# shutter_board.net
KiCad netlist of a schematic drawn in EAGLE
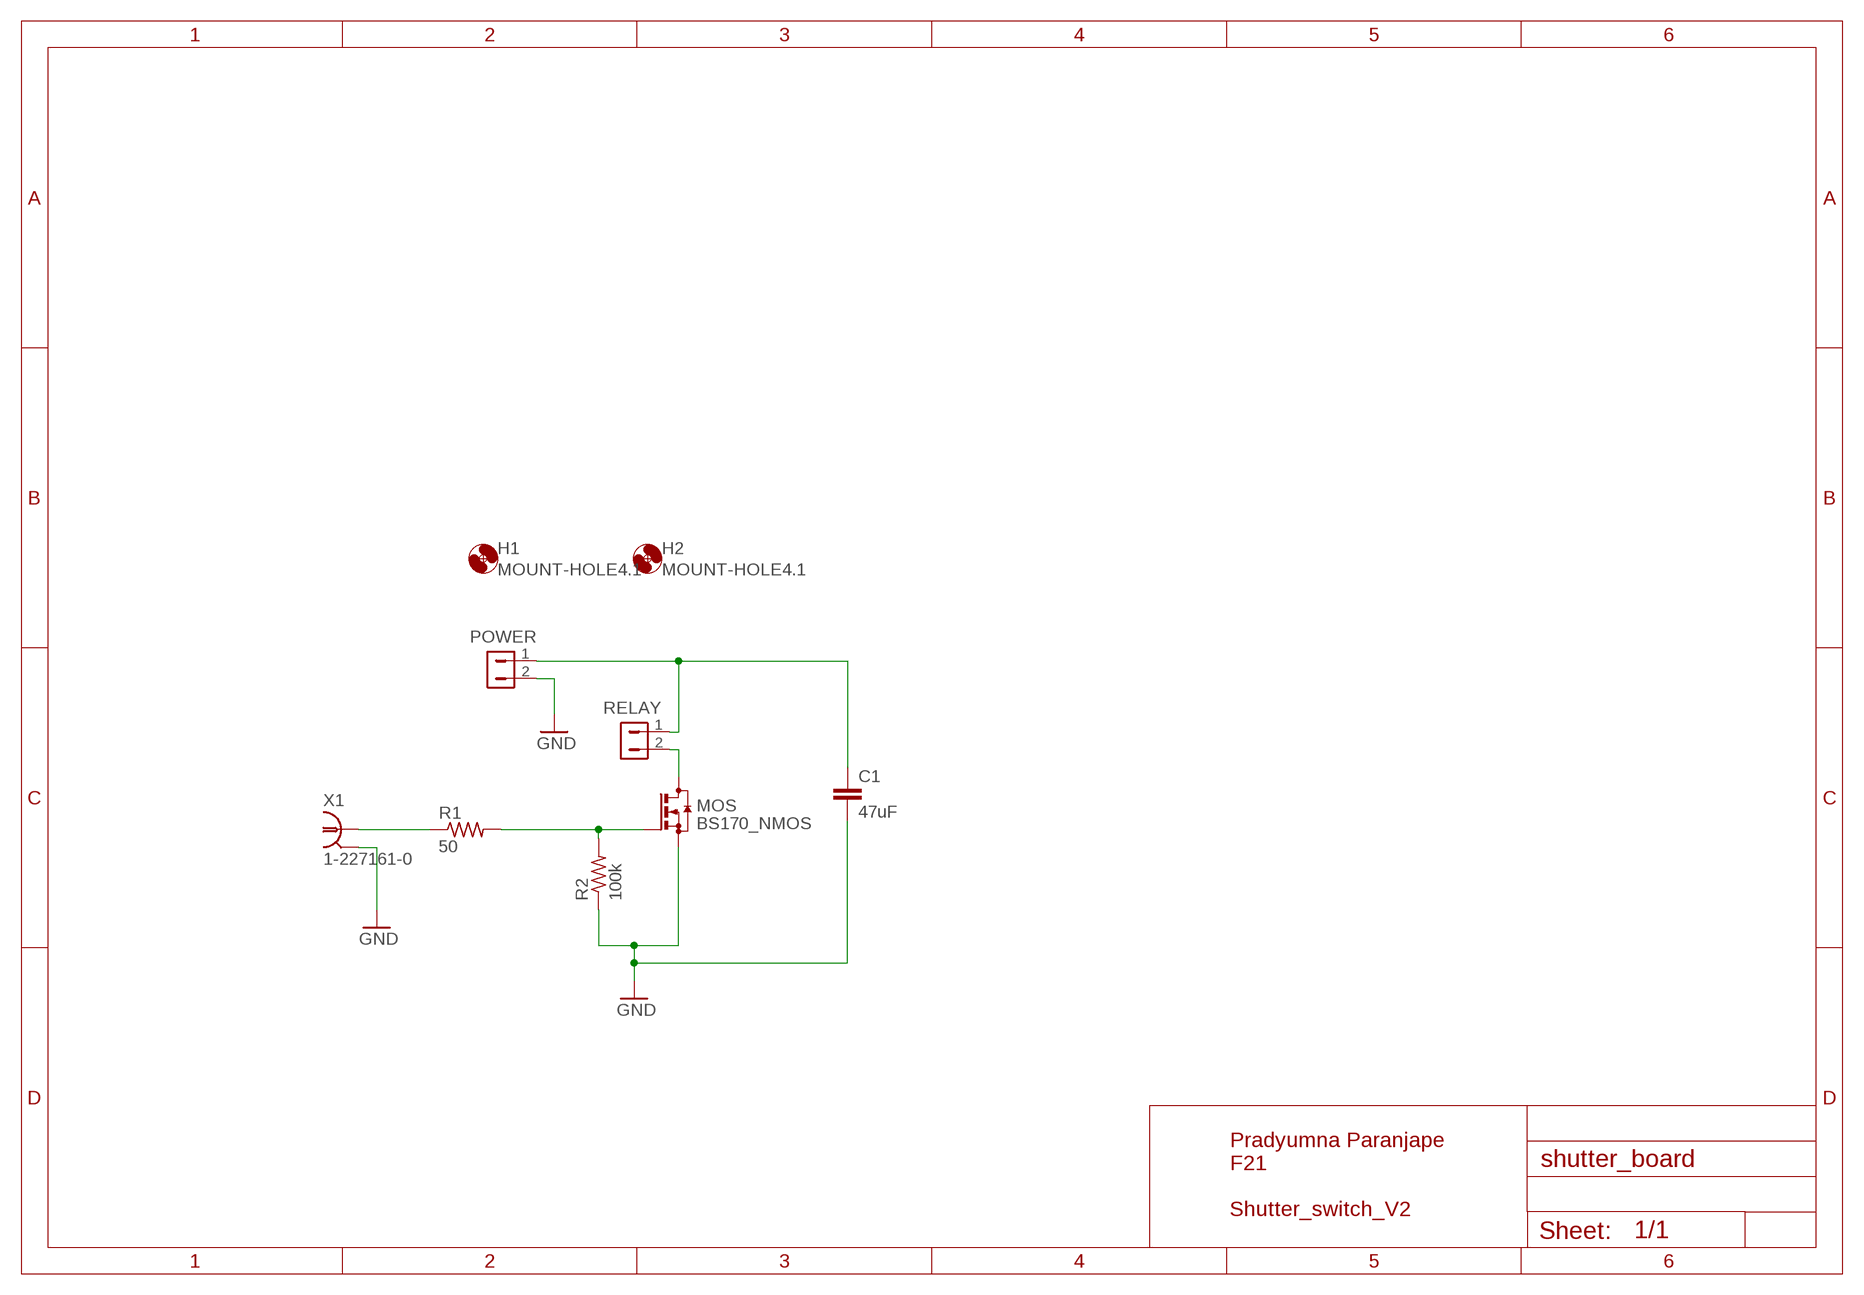
[diagram p0: schematic, sheet 1]

(export (version "E")
  (design (tool "Eeschema 10.0.6"))
  (components
    (comp (ref "C1")
      (value "47uF")
      (footprint "eagle-import:NALI_CAP")
      (libsource (lib "eagle-import") (part "NALI_CAPACITOR"))
    )
    (comp (ref "H1")
      (value "MOUNT-HOLE4.1")
      (footprint "eagle-import:4,1")
      (libsource (lib "eagle-import") (part "MOUNT-HOLE4.1"))
    )
    (comp (ref "H2")
      (value "MOUNT-HOLE4.1")
      (footprint "eagle-import:4,1")
      (libsource (lib "eagle-import") (part "MOUNT-HOLE4.1"))
    )
    (comp (ref "MOS")
      (value "BS170_NMOS")
      (footprint "eagle-import:TO92-3")
      (libsource (lib "eagle-import") (part "BS170_NMOS"))
    )
    (comp (ref "POWER")
      (value "2PIN_CONNECTOR")
      (footprint "eagle-import:KK2_MOLEX")
      (libsource (lib "eagle-import") (part "2PIN_CONNECTOR"))
    )
    (comp (ref "R1")
      (value "50")
      (footprint "eagle-import:SMALL_RESIS")
      (libsource (lib "eagle-import") (part "SMALL_RESIS"))
    )
    (comp (ref "R2")
      (value "100k")
      (footprint "eagle-import:SMALL_RESIS")
      (libsource (lib "eagle-import") (part "SMALL_RESIS"))
    )
    (comp (ref "RELAY")
      (value "2PIN_CONNECTOR")
      (footprint "eagle-import:KK2_MOLEX")
      (libsource (lib "eagle-import") (part "2PIN_CONNECTOR"))
    )
    (comp (ref "X1")
      (value "1-227161-0")
      (footprint "eagle-import:AMP_227161")
      (fields (field (name "MF") "TYCO ELECTRONICS") (field (name "MPN") "1-227161"))
      (libsource (lib "eagle-import") (part "?2271611--0"))
    )
  )
  (nets
    (net (code "1") (name "GND") (class "Default")
      (node (ref "C1") (pin "2") (pinfunction "2_2") (pintype "passive"))
      (node (ref "MOS") (pin "3") (pinfunction "S_3") (pintype "passive"))
      (node (ref "POWER") (pin "2") (pinfunction "4_2") (pintype "passive"))
      (node (ref "R2") (pin "1") (pinfunction "1_1") (pintype "passive"))
      (node (ref "X1") (pin "2") (pinfunction "2_2") (pintype "passive"))
    )
    (net (code "2") (name "Net-(MOS-D)") (class "Default")
      (node (ref "MOS") (pin "1") (pinfunction "D_1") (pintype "passive"))
      (node (ref "RELAY") (pin "2") (pinfunction "4_2") (pintype "passive"))
    )
    (net (code "3") (name "Net-(MOS-G)") (class "Default")
      (node (ref "MOS") (pin "2") (pinfunction "G_2") (pintype "passive"))
      (node (ref "R1") (pin "2") (pinfunction "2_2") (pintype "passive"))
      (node (ref "R2") (pin "2") (pinfunction "2_2") (pintype "passive"))
    )
    (net (code "4") (name "Net-(POWER-2)") (class "Default")
      (node (ref "C1") (pin "1") (pinfunction "1_1") (pintype "passive"))
      (node (ref "POWER") (pin "1") (pinfunction "2_1") (pintype "passive"))
      (node (ref "RELAY") (pin "1") (pinfunction "2_1") (pintype "passive"))
    )
    (net (code "5") (name "Net-(R1-Pad1)") (class "Default")
      (node (ref "R1") (pin "1") (pinfunction "1_1") (pintype "passive"))
      (node (ref "X1") (pin "1") (pinfunction "1_1") (pintype "passive"))
    )
  )
)
